# Gyrophare-CarteDeCommande.net
KiCad netlist of a schematic drawn in Altium Designer
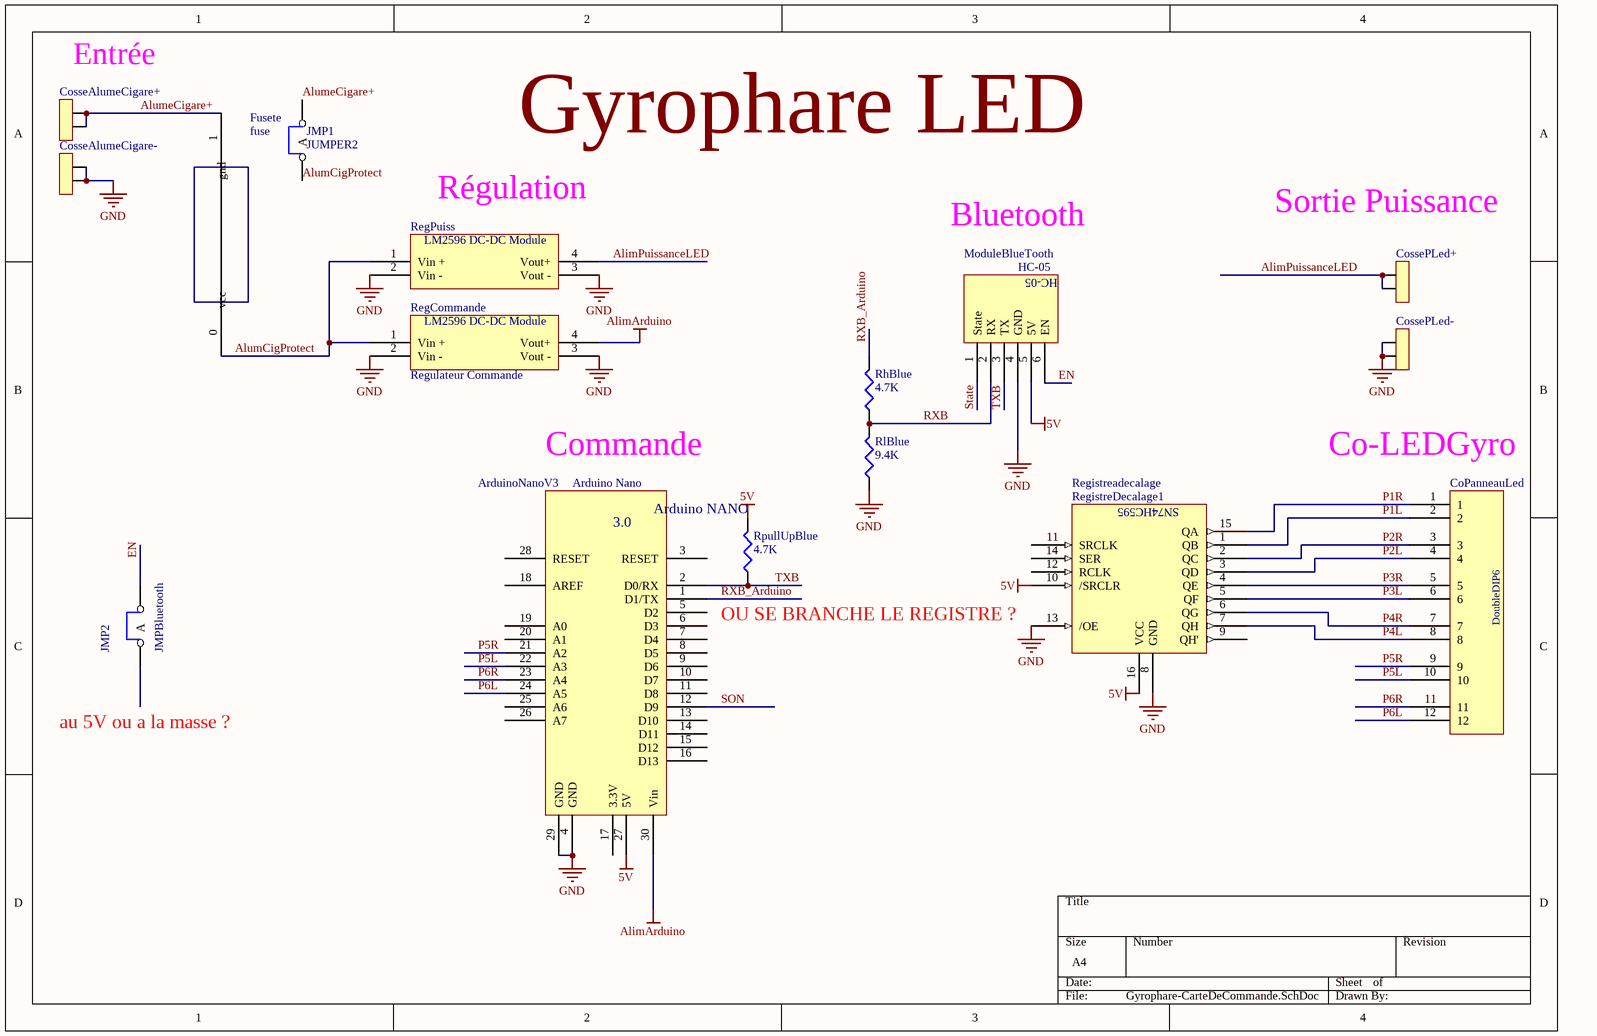
[diagram p0: Gyrophare-CarteDeCommande.SchDoc]

(export (version "E")
  (design (tool "Eeschema 10.0.6"))
  (components
    (comp (ref "ArduinoNanoV3")
      (value "Arduino Nano")
      (footprint "Arduino Nano FootPrint")
      (libsource (lib "Arduino Nano version") (part "Arduino Nano"))
    )
    (comp (ref "CoPanneauLed")
      (value "Co-DoubleDip6")
      (footprint "DoubleDIP6")
      (libsource (lib "Co-DoubleDip") (part "Co-DoubleDip6"))
    )
    (comp (ref "CosseAlumeCigare+")
      (value "CosseAlumeCigare+")
      (footprint "POWER2")
      (description "connecteur alim 2 pôles")
      (libsource (lib "ISEN_basics") (part "POWER2"))
    )
    (comp (ref "CosseAlumeCigare-")
      (value "CosseAlumeCigare+")
      (footprint "POWER2")
      (description "connecteur alim 2 pôles")
      (libsource (lib "ISEN_basics") (part "POWER2"))
    )
    (comp (ref "CossePLed+")
      (value "comment")
      (footprint "POWER2")
      (description "connecteur alim 2 pôles")
      (libsource (lib "") (part "POWER2_1"))
    )
    (comp (ref "CossePLed-")
      (value "comment")
      (footprint "POWER2")
      (description "connecteur alim 2 pôles")
      (libsource (lib "") (part "POWER2_1"))
    )
    (comp (ref "Fusete") (value "fuse") (footprint "FUSE") (libsource (lib "fuse") (part "Fuse")))
    (comp (ref "JMP1")
      (value "JUMPER2")
      (footprint "JMP2-100")
      (description "cavalier 1 position")
      (libsource (lib "ISEN_basics") (part "JUMPER2"))
    )
    (comp (ref "JMPBluetooth")
      (value "JMP2")
      (footprint "JMP2-100")
      (description "cavalier 1 position")
      (libsource (lib "ISEN_basics") (part "JUMPER2"))
    )
    (comp (ref "ModuleBlueTooth")
      (value "HC-05")
      (footprint "HC-05 Couché")
      (libsource (lib "ModuleBluetooth") (part "HC-05"))
    )
    (comp (ref "RegCommande")
      (value "Regulateur Commande")
      (footprint "Module LM2596 DC-DC")
      (libsource (lib "Régulateur de Tension LM2596") (part "Component_1"))
    )
    (comp (ref "RegistreDecalage1")
      (value "Registreadecalage")
      (footprint "74HC595")
      (libsource (lib "74HC595") (part "74HC595"))
    )
    (comp (ref "RegPuiss")
      (value "Regulateur Puissant")
      (footprint "Module LM2596 DC-DC")
      (libsource (lib "Régulateur de Tension LM2596") (part "Component_1"))
    )
    (comp (ref "RhBlue")
      (value "4.7K")
      (footprint "0805")
      (description "resistance")
      (fields (field (name "Comment") "RES"))
      (libsource (lib "ISEN_basics") (part "RES"))
    )
    (comp (ref "RlBlue")
      (value "9.4K")
      (footprint "0805")
      (description "resistance")
      (fields (field (name "Comment") "RES"))
      (libsource (lib "ISEN_basics") (part "RES"))
    )
    (comp (ref "RpullUpBlue")
      (value "4.7K")
      (footprint "0805")
      (description "resistance")
      (fields (field (name "Comment") "RES"))
      (libsource (lib "ISEN_basics") (part "RES"))
    )
  )
  (nets
    (net (code "1") (name "/AlimPuissanceLED") (class "Default")
      (node (ref "CossePLed+") (pin "1") (pintype "passive"))
      (node (ref "CossePLed+") (pin "2") (pintype "passive"))
      (node (ref "RegPuiss") (pin "4") (pinfunction "Vout+_4") (pintype "passive"))
    )
    (net (code "2") (name "/AlumCigProtect") (class "Default")
      (node (ref "Fusete") (pin "0") (pinfunction "vcc_0") (pintype "passive"))
      (node (ref "JMP1") (pin "1") (pinfunction "A_1") (pintype "passive"))
      (node (ref "RegCommande") (pin "1") (pinfunction "Vin_+_1") (pintype "passive"))
      (node (ref "RegPuiss") (pin "1") (pinfunction "Vin_+_1") (pintype "passive"))
    )
    (net (code "3") (name "/AlumeCigare+") (class "Default")
      (node (ref "CosseAlumeCigare+") (pin "1") (pintype "passive"))
      (node (ref "CosseAlumeCigare+") (pin "2") (pintype "passive"))
      (node (ref "Fusete") (pin "1") (pinfunction "gnd_1") (pintype "passive"))
      (node (ref "JMP1") (pin "2") (pinfunction "com_2") (pintype "passive"))
    )
    (net (code "4") (name "/EN") (class "Default")
      (node (ref "JMPBluetooth") (pin "2") (pinfunction "com_2") (pintype "passive"))
      (node (ref "ModuleBlueTooth") (pin "6") (pinfunction "EN_6") (pintype "passive"))
    )
    (net (code "5") (name "/P1L") (class "Default")
      (node (ref "CoPanneauLed") (pin "2") (pinfunction "2_2") (pintype "passive"))
      (node (ref "RegistreDecalage1") (pin "1") (pinfunction "QB_1") (pintype "output"))
    )
    (net (code "6") (name "/P1R") (class "Default")
      (node (ref "CoPanneauLed") (pin "1") (pinfunction "1_1") (pintype "passive"))
      (node (ref "RegistreDecalage1") (pin "15") (pinfunction "QA_15") (pintype "output"))
    )
    (net (code "7") (name "/P2L") (class "Default")
      (node (ref "CoPanneauLed") (pin "4") (pinfunction "4_4") (pintype "passive"))
      (node (ref "RegistreDecalage1") (pin "3") (pinfunction "QD_3") (pintype "output"))
    )
    (net (code "8") (name "/P2R") (class "Default")
      (node (ref "CoPanneauLed") (pin "3") (pinfunction "3_3") (pintype "passive"))
      (node (ref "RegistreDecalage1") (pin "2") (pinfunction "QC_2") (pintype "output"))
    )
    (net (code "9") (name "/P3L") (class "Default")
      (node (ref "CoPanneauLed") (pin "6") (pinfunction "6_6") (pintype "passive"))
      (node (ref "RegistreDecalage1") (pin "5") (pinfunction "QF_5") (pintype "output"))
    )
    (net (code "10") (name "/P3R") (class "Default")
      (node (ref "CoPanneauLed") (pin "5") (pinfunction "5_5") (pintype "passive"))
      (node (ref "RegistreDecalage1") (pin "4") (pinfunction "QE_4") (pintype "output"))
    )
    (net (code "11") (name "/P4L") (class "Default")
      (node (ref "CoPanneauLed") (pin "8") (pinfunction "8_8") (pintype "passive"))
      (node (ref "RegistreDecalage1") (pin "7") (pinfunction "QH_7") (pintype "output"))
    )
    (net (code "12") (name "/P4R") (class "Default")
      (node (ref "CoPanneauLed") (pin "7") (pinfunction "7_7") (pintype "passive"))
      (node (ref "RegistreDecalage1") (pin "6") (pinfunction "QG_6") (pintype "output"))
    )
    (net (code "13") (name "/P5L") (class "Default")
      (node (ref "ArduinoNanoV3") (pin "22") (pinfunction "A3_22") (pintype "passive"))
      (node (ref "CoPanneauLed") (pin "10") (pinfunction "10_10") (pintype "passive"))
    )
    (net (code "14") (name "/P5R") (class "Default")
      (node (ref "ArduinoNanoV3") (pin "21") (pinfunction "A2_21") (pintype "passive"))
      (node (ref "CoPanneauLed") (pin "9") (pinfunction "9_9") (pintype "passive"))
    )
    (net (code "15") (name "/P6L") (class "Default")
      (node (ref "ArduinoNanoV3") (pin "24") (pinfunction "A5_24") (pintype "passive"))
      (node (ref "CoPanneauLed") (pin "12") (pinfunction "12_12") (pintype "passive"))
    )
    (net (code "16") (name "/P6R") (class "Default")
      (node (ref "ArduinoNanoV3") (pin "23") (pinfunction "A4_23") (pintype "passive"))
      (node (ref "CoPanneauLed") (pin "11") (pinfunction "11_11") (pintype "passive"))
    )
    (net (code "17") (name "/RXB") (class "Default")
      (node (ref "ModuleBlueTooth") (pin "2") (pinfunction "RX_2") (pintype "passive"))
      (node (ref "RhBlue") (pin "1") (pintype "passive"))
      (node (ref "RlBlue") (pin "2") (pintype "passive"))
    )
    (net (code "18") (name "/RXB_Arduino") (class "Default")
      (node (ref "ArduinoNanoV3") (pin "1") (pinfunction "D1/TX_1") (pintype "passive"))
      (node (ref "RhBlue") (pin "2") (pintype "passive"))
    )
    (net (code "19") (name "/SON") (class "Default")
      (node (ref "ArduinoNanoV3") (pin "12") (pinfunction "D9_12") (pintype "passive"))
    )
    (net (code "20") (name "/State") (class "Default")
      (node (ref "ModuleBlueTooth") (pin "1") (pinfunction "State_1") (pintype "passive"))
    )
    (net (code "21") (name "/TXB") (class "Default")
      (node (ref "ArduinoNanoV3") (pin "2") (pinfunction "D0/RX_2") (pintype "passive"))
      (node (ref "ModuleBlueTooth") (pin "3") (pinfunction "TX_3") (pintype "passive"))
      (node (ref "RpullUpBlue") (pin "1") (pintype "passive"))
    )
    (net (code "22") (name "5V") (class "Default")
      (node (ref "ArduinoNanoV3") (pin "27") (pinfunction "5V_27") (pintype "passive"))
      (node (ref "ModuleBlueTooth") (pin "5") (pinfunction "5V_5") (pintype "passive"))
      (node (ref "RegistreDecalage1") (pin "10") (pinfunction "/SRCLR_10") (pintype "input"))
      (node (ref "RegistreDecalage1") (pin "16") (pinfunction "VCC_16") (pintype "passive"))
      (node (ref "RpullUpBlue") (pin "2") (pintype "passive"))
    )
    (net (code "23") (name "AlimArduino") (class "Default")
      (node (ref "ArduinoNanoV3") (pin "30") (pinfunction "Vin_30") (pintype "passive"))
      (node (ref "RegCommande") (pin "4") (pinfunction "Vout+_4") (pintype "passive"))
    )
    (net (code "24") (name "GND") (class "Default")
      (node (ref "ArduinoNanoV3") (pin "29") (pinfunction "GND_29") (pintype "passive"))
      (node (ref "ArduinoNanoV3") (pin "4") (pinfunction "GND_4") (pintype "passive"))
      (node (ref "CosseAlumeCigare-") (pin "1") (pintype "passive"))
      (node (ref "CosseAlumeCigare-") (pin "2") (pintype "passive"))
      (node (ref "CossePLed-") (pin "1") (pintype "passive"))
      (node (ref "CossePLed-") (pin "2") (pintype "passive"))
      (node (ref "ModuleBlueTooth") (pin "4") (pinfunction "GND_4") (pintype "passive"))
      (node (ref "RegCommande") (pin "2") (pinfunction "Vin_-_2") (pintype "passive"))
      (node (ref "RegCommande") (pin "3") (pinfunction "Vout_-_3") (pintype "passive"))
      (node (ref "RegPuiss") (pin "2") (pinfunction "Vin_-_2") (pintype "passive"))
      (node (ref "RegPuiss") (pin "3") (pinfunction "Vout_-_3") (pintype "passive"))
      (node (ref "RegistreDecalage1") (pin "13") (pinfunction "/OE_13") (pintype "input"))
      (node (ref "RegistreDecalage1") (pin "8") (pinfunction "GND_8") (pintype "passive"))
      (node (ref "RlBlue") (pin "1") (pintype "passive"))
    )
    (net (code "25") (name "unconnected-(ArduinoNanoV3-3.3V-Pad17)") (class "Default")
      (node (ref "ArduinoNanoV3") (pin "17") (pinfunction "3.3V_17") (pintype "passive"))
    )
    (net (code "26") (name "unconnected-(ArduinoNanoV3-A0-Pad19)") (class "Default")
      (node (ref "ArduinoNanoV3") (pin "19") (pinfunction "A0_19") (pintype "passive"))
    )
    (net (code "27") (name "unconnected-(ArduinoNanoV3-A1-Pad20)") (class "Default")
      (node (ref "ArduinoNanoV3") (pin "20") (pinfunction "A1_20") (pintype "passive"))
    )
    (net (code "28") (name "unconnected-(ArduinoNanoV3-A6-Pad25)") (class "Default")
      (node (ref "ArduinoNanoV3") (pin "25") (pinfunction "A6_25") (pintype "passive"))
    )
    (net (code "29") (name "unconnected-(ArduinoNanoV3-A7-Pad26)") (class "Default")
      (node (ref "ArduinoNanoV3") (pin "26") (pinfunction "A7_26") (pintype "passive"))
    )
    (net (code "30") (name "unconnected-(ArduinoNanoV3-AREF-Pad18)") (class "Default")
      (node (ref "ArduinoNanoV3") (pin "18") (pinfunction "AREF_18") (pintype "passive"))
    )
    (net (code "31") (name "unconnected-(ArduinoNanoV3-D2-Pad5)") (class "Default")
      (node (ref "ArduinoNanoV3") (pin "5") (pinfunction "D2_5") (pintype "passive"))
    )
    (net (code "32") (name "unconnected-(ArduinoNanoV3-D3-Pad6)") (class "Default")
      (node (ref "ArduinoNanoV3") (pin "6") (pinfunction "D3_6") (pintype "passive"))
    )
    (net (code "33") (name "unconnected-(ArduinoNanoV3-D4-Pad7)") (class "Default")
      (node (ref "ArduinoNanoV3") (pin "7") (pinfunction "D4_7") (pintype "passive"))
    )
    (net (code "34") (name "unconnected-(ArduinoNanoV3-D5-Pad8)") (class "Default")
      (node (ref "ArduinoNanoV3") (pin "8") (pinfunction "D5_8") (pintype "passive"))
    )
    (net (code "35") (name "unconnected-(ArduinoNanoV3-D6-Pad9)") (class "Default")
      (node (ref "ArduinoNanoV3") (pin "9") (pinfunction "D6_9") (pintype "passive"))
    )
    (net (code "36") (name "unconnected-(ArduinoNanoV3-D7-Pad10)") (class "Default")
      (node (ref "ArduinoNanoV3") (pin "10") (pinfunction "D7_10") (pintype "passive"))
    )
    (net (code "37") (name "unconnected-(ArduinoNanoV3-D8-Pad11)") (class "Default")
      (node (ref "ArduinoNanoV3") (pin "11") (pinfunction "D8_11") (pintype "passive"))
    )
    (net (code "38") (name "unconnected-(ArduinoNanoV3-D10-Pad13)") (class "Default")
      (node (ref "ArduinoNanoV3") (pin "13") (pinfunction "D10_13") (pintype "passive"))
    )
    (net (code "39") (name "unconnected-(ArduinoNanoV3-D11-Pad14)") (class "Default")
      (node (ref "ArduinoNanoV3") (pin "14") (pinfunction "D11_14") (pintype "passive"))
    )
    (net (code "40") (name "unconnected-(ArduinoNanoV3-D12-Pad15)") (class "Default")
      (node (ref "ArduinoNanoV3") (pin "15") (pinfunction "D12_15") (pintype "passive"))
    )
    (net (code "41") (name "unconnected-(ArduinoNanoV3-D13-Pad16)") (class "Default")
      (node (ref "ArduinoNanoV3") (pin "16") (pinfunction "D13_16") (pintype "passive"))
    )
    (net (code "42") (name "unconnected-(ArduinoNanoV3-RESET-Pad3)") (class "Default")
      (node (ref "ArduinoNanoV3") (pin "3") (pinfunction "RESET_3") (pintype "passive"))
    )
    (net (code "43") (name "unconnected-(ArduinoNanoV3-RESET-Pad28)") (class "Default")
      (node (ref "ArduinoNanoV3") (pin "28") (pinfunction "RESET_28") (pintype "passive"))
    )
    (net (code "44") (name "unconnected-(JMPBluetooth-A-Pad1)") (class "Default")
      (node (ref "JMPBluetooth") (pin "1") (pinfunction "A_1") (pintype "passive"))
    )
    (net (code "45") (name "unconnected-(RegistreDecalage1-QH'-Pad9)") (class "Default")
      (node (ref "RegistreDecalage1") (pin "9") (pinfunction "QH'_9") (pintype "output"))
    )
    (net (code "46") (name "unconnected-(RegistreDecalage1-RCLK-Pad12)") (class "Default")
      (node (ref "RegistreDecalage1") (pin "12") (pinfunction "RCLK_12") (pintype "input"))
    )
    (net (code "47") (name "unconnected-(RegistreDecalage1-SER-Pad14)") (class "Default")
      (node (ref "RegistreDecalage1") (pin "14") (pinfunction "SER_14") (pintype "input"))
    )
    (net (code "48") (name "unconnected-(RegistreDecalage1-SRCLK-Pad11)") (class "Default")
      (node (ref "RegistreDecalage1") (pin "11") (pinfunction "SRCLK_11") (pintype "input"))
    )
  )
)
